# FPGA.net
KiCad netlist of a schematic drawn in Altium Designer
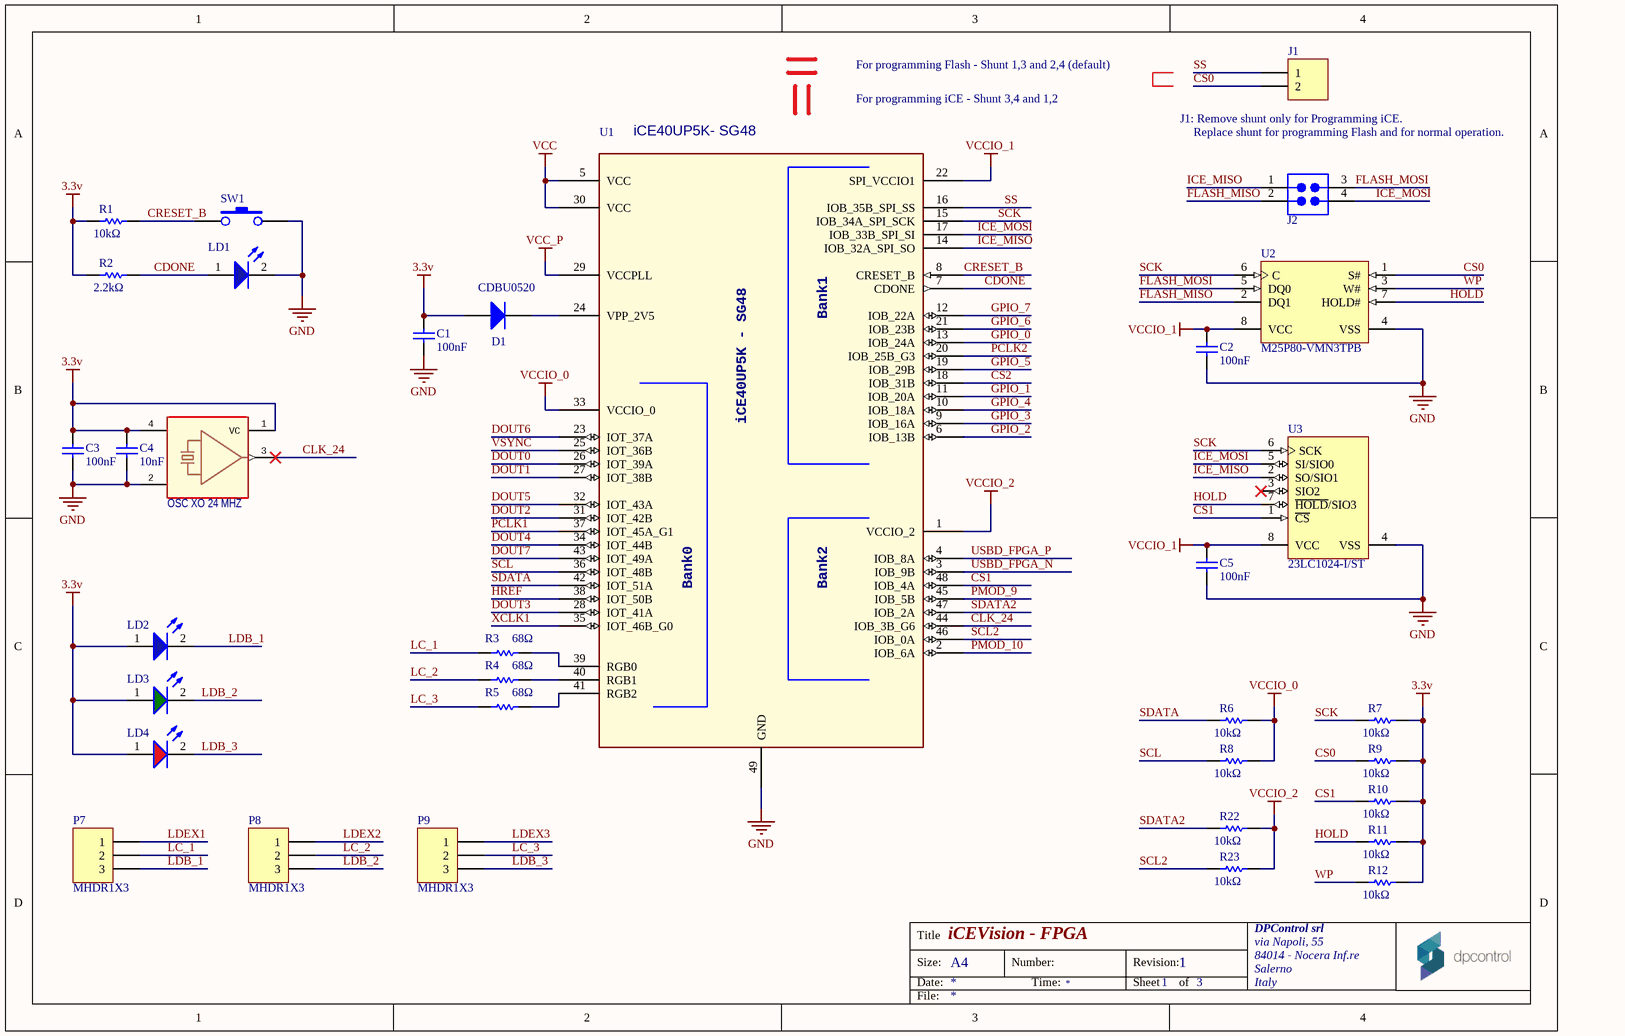
[diagram p0: FPGA.SchDoc]

(export (version "E")
  (design (tool "Eeschema 10.0.6"))
  (components
    (comp (ref "C1")
      (value "100nF")
      (footprint "0603")
      (description "Ceramic Chip Capacitor - Standard")
      (fields
        (field (name "PART NO") "C0603C104K8RACTU")
        (field (name "MPN") "GPC0603104")
        (field (name "PUBLISHER") "Altium Limited")
      )
      (libsource (lib "KEMET Chip Capacitor") (part "C0603"))
    )
    (comp (ref "C2")
      (value "100nF")
      (footprint "0603")
      (description "Ceramic Chip Capacitor - Standard")
      (fields
        (field (name "PART NO") "C0603C104K8RACTU")
        (field (name "MPN") "GPC0603104")
        (field (name "PUBLISHER") "Altium Limited")
      )
      (libsource (lib "KEMET Chip Capacitor") (part "C0603"))
    )
    (comp (ref "C3")
      (value "100nF")
      (footprint "0603")
      (description "Ceramic Chip Capacitor - Standard")
      (fields
        (field (name "PART NO") "C0603C104K8RACTU")
        (field (name "MPN") "GPC0603104")
        (field (name "PUBLISHER") "Altium Limited")
      )
      (libsource (lib "KEMET Chip Capacitor") (part "C0603"))
    )
    (comp (ref "C4")
      (value "10nF")
      (footprint "0603")
      (description "Ceramic Chip Capacitor - Standard")
      (fields
        (field (name "PART NO") "C0603C103K5RACTU")
        (field (name "MPN") "GPC0603103")
        (field (name "PUBLISHER") "Altium Limited")
      )
      (libsource (lib "KEMET Chip Capacitor") (part "C0603"))
    )
    (comp (ref "C5")
      (value "100nF")
      (footprint "0603")
      (description "Ceramic Chip Capacitor - Standard")
      (fields
        (field (name "PART NO") "C0603C104K8RACTU")
        (field (name "MPN") "GPC0603104")
        (field (name "PUBLISHER") "Altium Limited")
      )
      (libsource (lib "KEMET Chip Capacitor") (part "C0603"))
    )
    (comp (ref "D1")
      (value "CDBU0520")
      (footprint "0603")
      (description "Default Diode")
      (fields
        (field (name "MANUFACTURER") "COMCHIP TECHNOLOGY")
        (field (name "Comment") "Diode")
        (field (name "PUBLISHER") "Altium Limited")
      )
      (libsource (lib "Miscellaneous Devices_DPC") (part "Diode"))
    )
    (comp (ref "J1")
      (value "WE-2.54 mm Pin Header & Jumper 61300211121")
      (footprint "61300211121")
      (description "WR-PHD 2.54mm Pin Header")
      (fields
        (field (name "MANUFACTURER") "Würth Elektronik eiSos GmbH")
        (field (name "PARTNO") "61300211121")
        (field (name "CREATED BY") "Karrer Zheng")
      )
      (libsource (lib "WE_WR-PHD_Pin Header_2.54mm_rev15c") (part "WE-2.54 mm Pin Header & Jumper 61300211121"))
    )
    (comp (ref "J2")
      (value "WE-2.54 mm Pin Header & Jumper 61300421121")
      (footprint "61300421121")
      (description "WR-PHD 2.54 mm Dual Pin Header")
      (fields
        (field (name "MANUFACTURER") "Würth Elektronik eiSos GmbH")
        (field (name "PARTNO") "61300421121")
        (field (name "CREATED BY") "Karrer Zheng")
      )
      (libsource (lib "WE_WR-PHD_Pin Header_2.54mm_rev15c") (part "WE-2.54 mm Pin Header & Jumper 61300421121"))
    )
    (comp (ref "LD1")
      (value "150060BS75000")
      (footprint "LED_0603_Blue")
      (description "SMD mono-color Chip LED, WL-SMCW, Blue")
      (fields
        (field (name "MANUFACTURER") "W黵th Elektronik eiSos GmbH")
        (field (name "CREATED BY") "Christin Otto")
      )
      (libsource (lib "WL-LEDsmd") (part "WL-SMCW 0603  150060BS75000"))
    )
    (comp (ref "LD2")
      (value "150060BS75000")
      (footprint "LED_0603_Blue")
      (description "SMD mono-color Chip LED, WL-SMCW, Blue")
      (fields
        (field (name "MANUFACTURER") "W黵th Elektronik eiSos GmbH")
        (field (name "CREATED BY") "Christin Otto")
      )
      (libsource (lib "WL-LEDsmd") (part "WL-SMCW 0603  150060BS75000"))
    )
    (comp (ref "LD3")
      (value "150060GS75000")
      (footprint "LED_0603_Green")
      (description "SMD mono-color Chip LED, WL-SMCW, Green")
      (fields
        (field (name "MANUFACTURER") "W黵th Elektronik eiSos GmbH")
        (field (name "CREATED BY") "Christin Otto")
      )
      (libsource (lib "WL-LEDsmd") (part "WL-SMCW 0603  150060GS75000"))
    )
    (comp (ref "LD4")
      (value "150060RS75000")
      (footprint "LED_0603_Red")
      (description "SMD mono-color Chip LED, WL-SMCW, Red")
      (fields
        (field (name "MANUFACTURER") "W黵th Elektronik eiSos GmbH")
        (field (name "CREATED BY") "Christin Otto")
      )
      (libsource (lib "WL-LEDsmd") (part "WL-SMCW 0603  150060RS75000"))
    )
    (comp (ref "OSC1")
      (value "OSC XO 24 MHZ")
      (footprint "3.4X2.7-4-PAD")
      (fields
        (field (name "MANUFACTURER") "Abracon LLC")
        (field (name "PART NO") "LFSPXO025558")
        (field (name "MPN") "7M-24.000MAAJ-T")
      )
      (libsource (lib "IQD-Frequency-Products") (part "TCXO-CFPT-9301"))
    )
    (comp (ref "P7")
      (value "MHDR1X3")
      (footprint "MHDR1X3")
      (description "Header, 3-Pin")
      (fields (field (name "PUBLISHER") "Altium Limited"))
      (libsource (lib "Miscellaneous Connectors") (part "MHDR1X3"))
    )
    (comp (ref "P8")
      (value "MHDR1X3")
      (footprint "MHDR1X3")
      (description "Header, 3-Pin")
      (fields (field (name "PUBLISHER") "Altium Limited"))
      (libsource (lib "Miscellaneous Connectors") (part "MHDR1X3"))
    )
    (comp (ref "P9")
      (value "MHDR1X3")
      (footprint "MHDR1X3")
      (description "Header, 3-Pin")
      (fields (field (name "PUBLISHER") "Altium Limited"))
      (libsource (lib "Miscellaneous Connectors") (part "MHDR1X3"))
    )
    (comp (ref "R1")
      (value "10kΩ")
      (footprint "3-0603")
      (fields
        (field (name "PART NO") "ERJ3EKF1002V")
        (field (name "MPN") "GPR060310K")
        (field (name "Comment") "ERJ3EK")
        (field (name "PUBLISHER") "Altium Limited")
      )
      (libsource (lib "Panasonic Resistor") (part "ERJ3EK"))
    )
    (comp (ref "R2")
      (value "2.2kΩ")
      (footprint "3-0603")
      (fields
        (field (name "PART NO") "ERA3ARB222V")
        (field (name "MPN") "GPR06032K2")
        (field (name "Comment") "ERJ3EK")
        (field (name "PUBLISHER") "Altium Limited")
      )
      (libsource (lib "Panasonic Resistor") (part "ERJ3EK"))
    )
    (comp (ref "R3")
      (value "68Ω")
      (footprint "3-0603")
      (fields
        (field (name "PART NO") "ERJPA3F68R0V")
        (field (name "MPN") "GPR060368R")
        (field (name "Comment") "ERJ3EK")
        (field (name "PUBLISHER") "Altium Limited")
      )
      (libsource (lib "Panasonic Resistor") (part "ERJ3EK"))
    )
    (comp (ref "R4")
      (value "68Ω")
      (footprint "3-0603")
      (fields
        (field (name "PART NO") "ERJPA3F68R0V")
        (field (name "MPN") "GPR060368R")
        (field (name "Comment") "ERJ3EK")
        (field (name "PUBLISHER") "Altium Limited")
      )
      (libsource (lib "Panasonic Resistor") (part "ERJ3EK"))
    )
    (comp (ref "R5")
      (value "68Ω")
      (footprint "3-0603")
      (fields
        (field (name "PART NO") "ERJPA3F68R0V")
        (field (name "MPN") "GPR060368R")
        (field (name "Comment") "ERJ3EK")
        (field (name "PUBLISHER") "Altium Limited")
      )
      (libsource (lib "Panasonic Resistor") (part "ERJ3EK"))
    )
    (comp (ref "R6")
      (value "10kΩ")
      (footprint "3-0603")
      (fields
        (field (name "PART NO") "ERJ3EKF1002V")
        (field (name "MPN") "GPR060310K")
        (field (name "Comment") "ERJ3EK")
        (field (name "PUBLISHER") "Altium Limited")
      )
      (libsource (lib "Panasonic Resistor") (part "ERJ3EK"))
    )
    (comp (ref "R7")
      (value "10kΩ")
      (footprint "3-0603")
      (fields
        (field (name "PART NO") "ERJ3EKF1002V")
        (field (name "MPN") "GPR060310K")
        (field (name "Comment") "ERJ3EK")
        (field (name "PUBLISHER") "Altium Limited")
      )
      (libsource (lib "Panasonic Resistor") (part "ERJ3EK"))
    )
    (comp (ref "R8")
      (value "10kΩ")
      (footprint "3-0603")
      (fields
        (field (name "PART NO") "ERJ3EKF1002V")
        (field (name "MPN") "GPR060310K")
        (field (name "Comment") "ERJ3EK")
        (field (name "PUBLISHER") "Altium Limited")
      )
      (libsource (lib "Panasonic Resistor") (part "ERJ3EK"))
    )
    (comp (ref "R9")
      (value "10kΩ")
      (footprint "3-0603")
      (fields
        (field (name "PART NO") "ERJ3EKF1002V")
        (field (name "MPN") "GPR060310K")
        (field (name "Comment") "ERJ3EK")
        (field (name "PUBLISHER") "Altium Limited")
      )
      (libsource (lib "Panasonic Resistor") (part "ERJ3EK"))
    )
    (comp (ref "R10")
      (value "10kΩ")
      (footprint "3-0603")
      (fields
        (field (name "PART NO") "ERJ3EKF1002V")
        (field (name "MPN") "GPR060310K")
        (field (name "Comment") "ERJ3EK")
        (field (name "PUBLISHER") "Altium Limited")
      )
      (libsource (lib "Panasonic Resistor") (part "ERJ3EK"))
    )
    (comp (ref "R11")
      (value "10kΩ")
      (footprint "3-0603")
      (fields
        (field (name "PART NO") "ERJ3EKF1002V")
        (field (name "MPN") "GPR060310K")
        (field (name "Comment") "ERJ3EK")
        (field (name "PUBLISHER") "Altium Limited")
      )
      (libsource (lib "Panasonic Resistor") (part "ERJ3EK"))
    )
    (comp (ref "R12")
      (value "10kΩ")
      (footprint "3-0603")
      (fields
        (field (name "PART NO") "ERJ3EKF1002V")
        (field (name "MPN") "GPR060310K")
        (field (name "Comment") "ERJ3EK")
        (field (name "PUBLISHER") "Altium Limited")
      )
      (libsource (lib "Panasonic Resistor") (part "ERJ3EK"))
    )
    (comp (ref "R22")
      (value "10kΩ")
      (footprint "3-0603")
      (fields
        (field (name "PART NO") "ERJ3EKF1002V")
        (field (name "MPN") "GPR060310K")
        (field (name "Comment") "ERJ3EK")
        (field (name "PUBLISHER") "Altium Limited")
      )
      (libsource (lib "Panasonic Resistor") (part "ERJ3EK"))
    )
    (comp (ref "R23")
      (value "10kΩ")
      (footprint "3-0603")
      (fields
        (field (name "PART NO") "ERJ3EKF1002V")
        (field (name "MPN") "GPR060310K")
        (field (name "Comment") "ERJ3EK")
        (field (name "PUBLISHER") "Altium Limited")
      )
      (libsource (lib "Panasonic Resistor") (part "ERJ3EK"))
    )
    (comp (ref "SW1")
      (value "B3U-1000P")
      (footprint "B3U-1000P omron")
      (description "Tact Switch")
      (libsource (lib "B3U-1000P") (part "SW-PB"))
    )
    (comp (ref "U1")
      (value "iCE40UP5K- SG48")
      (fields (field (name "MPN") "ICE40UP5K-SG48ITR50"))
      (libsource (lib "LATTICEPLDS_Library") (part "iCE40UP5K- SG48"))
    )
    (comp (ref "U2")
      (value "M25P80-VMN3TPB")
      (footprint "MICT-MN-8_N")
      (fields
        (field (name "VOLTAGE") "2.7V-3.6V ")
        (field (name "MANUFACTURER") "Micron")
        (field (name "MPN") "MX25L8006EM2I-12G")
      )
      (libsource (lib "Micron Memory Serial NOR Flash") (part "M25P80-VMN3TPB"))
    )
    (comp (ref "U3")
      (value "23LC1024-I/ST")
      (footprint "MCHP-TSSOP-ST8_N")
      (fields (field (name "MANUFACTURER") "Microchip"))
      (libsource (lib "Microchip Serial SRAM") (part "23LC1024-I/ST"))
    )
  )
  (nets
    (net (code "1") (name "/CDONE") (class "Default")
      (node (ref "LD1") (pin "1") (pinfunction "A_1") (pintype "passive"))
      (node (ref "R2") (pin "2") (pinfunction "2_2") (pintype "passive"))
      (node (ref "U1") (pin "7") (pinfunction "CDONE_7") (pintype "output"))
    )
    (net (code "2") (name "/CLK_24") (class "Default")
      (node (ref "OSC1") (pin "3") (pinfunction "OUT_3") (pintype "output"))
      (node (ref "U1") (pin "44") (pinfunction "IOB_3B_G6_44") (pintype "bidirectional"))
    )
    (net (code "3") (name "/CRESET_B") (class "Default")
      (node (ref "R1") (pin "2") (pinfunction "2_2") (pintype "passive"))
      (node (ref "SW1") (pin "1") (pinfunction "1_1") (pintype "passive"))
      (node (ref "U1") (pin "8") (pinfunction "CRESET_B_8") (pintype "input"))
    )
    (net (code "4") (name "/CS0") (class "Default")
      (node (ref "J1") (pin "2") (pinfunction "2_2") (pintype "passive"))
      (node (ref "R9") (pin "1") (pinfunction "1_1") (pintype "passive"))
      (node (ref "U2") (pin "1") (pinfunction "S#_1") (pintype "input"))
    )
    (net (code "5") (name "/CS1") (class "Default")
      (node (ref "R10") (pin "1") (pinfunction "1_1") (pintype "passive"))
      (node (ref "U1") (pin "48") (pinfunction "IOB_4A_48") (pintype "bidirectional"))
      (node (ref "U3") (pin "1") (pinfunction "~{CS}_1") (pintype "input"))
    )
    (net (code "6") (name "/CS2") (class "Default")
      (node (ref "U1") (pin "18") (pinfunction "IOB_31B_18") (pintype "bidirectional"))
    )
    (net (code "7") (name "/DOUT0") (class "Default")
      (node (ref "U1") (pin "26") (pinfunction "IOT_39A_26") (pintype "bidirectional"))
    )
    (net (code "8") (name "/DOUT1") (class "Default")
      (node (ref "U1") (pin "27") (pinfunction "IOT_38B_27") (pintype "bidirectional"))
    )
    (net (code "9") (name "/DOUT2") (class "Default")
      (node (ref "U1") (pin "31") (pinfunction "IOT_42B_31") (pintype "bidirectional"))
    )
    (net (code "10") (name "/DOUT3") (class "Default")
      (node (ref "U1") (pin "28") (pinfunction "IOT_41A_28") (pintype "bidirectional"))
    )
    (net (code "11") (name "/DOUT4") (class "Default")
      (node (ref "U1") (pin "34") (pinfunction "IOT_44B_34") (pintype "bidirectional"))
    )
    (net (code "12") (name "/DOUT5") (class "Default")
      (node (ref "U1") (pin "32") (pinfunction "IOT_43A_32") (pintype "bidirectional"))
    )
    (net (code "13") (name "/DOUT6") (class "Default")
      (node (ref "U1") (pin "23") (pinfunction "IOT_37A_23") (pintype "bidirectional"))
    )
    (net (code "14") (name "/DOUT7") (class "Default")
      (node (ref "U1") (pin "43") (pinfunction "IOT_49A_43") (pintype "bidirectional"))
    )
    (net (code "15") (name "/FLASH_MISO") (class "Default")
      (node (ref "J2") (pin "2") (pinfunction "1_2") (pintype "passive"))
      (node (ref "U2") (pin "2") (pinfunction "DQ1_2") (pintype "tri_state"))
    )
    (net (code "16") (name "/FLASH_MOSI") (class "Default")
      (node (ref "J2") (pin "3") (pinfunction "3_3") (pintype "passive"))
      (node (ref "U2") (pin "5") (pinfunction "DQ0_5") (pintype "input"))
    )
    (net (code "17") (name "/GPIO_0") (class "Default")
      (node (ref "U1") (pin "13") (pinfunction "IOB_24A_13") (pintype "bidirectional"))
    )
    (net (code "18") (name "/GPIO_1") (class "Default")
      (node (ref "U1") (pin "11") (pinfunction "IOB_20A_11") (pintype "bidirectional"))
    )
    (net (code "19") (name "/GPIO_2") (class "Default")
      (node (ref "U1") (pin "6") (pinfunction "IOB_13B_6") (pintype "bidirectional"))
    )
    (net (code "20") (name "/GPIO_3") (class "Default")
      (node (ref "U1") (pin "9") (pinfunction "IOB_16A_9") (pintype "bidirectional"))
    )
    (net (code "21") (name "/GPIO_4") (class "Default")
      (node (ref "U1") (pin "10") (pinfunction "IOB_18A_10") (pintype "bidirectional"))
    )
    (net (code "22") (name "/GPIO_5") (class "Default")
      (node (ref "U1") (pin "19") (pinfunction "IOB_29B_19") (pintype "bidirectional"))
    )
    (net (code "23") (name "/GPIO_6") (class "Default")
      (node (ref "U1") (pin "21") (pinfunction "IOB_23B_21") (pintype "bidirectional"))
    )
    (net (code "24") (name "/GPIO_7") (class "Default")
      (node (ref "U1") (pin "12") (pinfunction "IOB_22A_12") (pintype "bidirectional"))
    )
    (net (code "25") (name "/HOLD") (class "Default")
      (node (ref "R11") (pin "1") (pinfunction "1_1") (pintype "passive"))
      (node (ref "U2") (pin "7") (pinfunction "HOLD#_7") (pintype "input"))
      (node (ref "U3") (pin "7") (pinfunction "~{HOLD}/SIO3_7") (pintype "bidirectional"))
    )
    (net (code "26") (name "/HREF") (class "Default")
      (node (ref "U1") (pin "38") (pinfunction "IOT_50B_38") (pintype "bidirectional"))
    )
    (net (code "27") (name "/ICE_MISO") (class "Default")
      (node (ref "J2") (pin "1") (pinfunction "2_1") (pintype "passive"))
      (node (ref "U1") (pin "14") (pinfunction "IOB_32A_SPI_SO_14") (pintype "passive"))
      (node (ref "U3") (pin "2") (pinfunction "SO/SIO1_2") (pintype "bidirectional"))
    )
    (net (code "28") (name "/ICE_MOSI") (class "Default")
      (node (ref "J2") (pin "4") (pinfunction "4_4") (pintype "passive"))
      (node (ref "U1") (pin "17") (pinfunction "IOB_33B_SPI_SI_17") (pintype "passive"))
      (node (ref "U3") (pin "5") (pinfunction "SI/SIO0_5") (pintype "bidirectional"))
    )
    (net (code "29") (name "/LC_1") (class "Default")
      (node (ref "P7") (pin "2") (pinfunction "2_2") (pintype "passive"))
      (node (ref "R3") (pin "1") (pinfunction "1_1") (pintype "passive"))
    )
    (net (code "30") (name "/LC_2") (class "Default")
      (node (ref "P8") (pin "2") (pinfunction "2_2") (pintype "passive"))
      (node (ref "R4") (pin "1") (pinfunction "1_1") (pintype "passive"))
    )
    (net (code "31") (name "/LC_3") (class "Default")
      (node (ref "P9") (pin "2") (pinfunction "2_2") (pintype "passive"))
      (node (ref "R5") (pin "1") (pinfunction "1_1") (pintype "passive"))
    )
    (net (code "32") (name "/LDB_1") (class "Default")
      (node (ref "LD2") (pin "2") (pinfunction "C_2") (pintype "passive"))
      (node (ref "P7") (pin "3") (pinfunction "3_3") (pintype "passive"))
    )
    (net (code "33") (name "/LDB_2") (class "Default")
      (node (ref "LD3") (pin "2") (pinfunction "C_2") (pintype "passive"))
      (node (ref "P8") (pin "3") (pinfunction "3_3") (pintype "passive"))
    )
    (net (code "34") (name "/LDB_3") (class "Default")
      (node (ref "LD4") (pin "2") (pinfunction "C_2") (pintype "passive"))
      (node (ref "P9") (pin "3") (pinfunction "3_3") (pintype "passive"))
    )
    (net (code "35") (name "/LDEX1") (class "Default")
      (node (ref "P7") (pin "1") (pinfunction "1_1") (pintype "passive"))
    )
    (net (code "36") (name "/LDEX2") (class "Default")
      (node (ref "P8") (pin "1") (pinfunction "1_1") (pintype "passive"))
    )
    (net (code "37") (name "/LDEX3") (class "Default")
      (node (ref "P9") (pin "1") (pinfunction "1_1") (pintype "passive"))
    )
    (net (code "38") (name "/PCLK1") (class "Default")
      (node (ref "U1") (pin "37") (pinfunction "IOT_45A_G1_37") (pintype "bidirectional"))
    )
    (net (code "39") (name "/PCLK2") (class "Default")
      (node (ref "U1") (pin "20") (pinfunction "IOB_25B_G3_20") (pintype "bidirectional"))
    )
    (net (code "40") (name "/PMOD_9") (class "Default")
      (node (ref "U1") (pin "45") (pinfunction "IOB_5B_45") (pintype "bidirectional"))
    )
    (net (code "41") (name "/PMOD_10") (class "Default")
      (node (ref "U1") (pin "2") (pinfunction "IOB_6A_2") (pintype "bidirectional"))
    )
    (net (code "42") (name "/SCK") (class "Default")
      (node (ref "R7") (pin "1") (pinfunction "1_1") (pintype "passive"))
      (node (ref "U1") (pin "15") (pinfunction "IOB_34A_SPI_SCK_15") (pintype "passive"))
      (node (ref "U2") (pin "6") (pinfunction "C_6") (pintype "input"))
      (node (ref "U3") (pin "6") (pinfunction "SCK_6") (pintype "input"))
    )
    (net (code "43") (name "/SCL") (class "Default")
      (node (ref "R8") (pin "1") (pinfunction "1_1") (pintype "passive"))
      (node (ref "U1") (pin "36") (pinfunction "IOT_48B_36") (pintype "bidirectional"))
    )
    (net (code "44") (name "/SCL2") (class "Default")
      (node (ref "R23") (pin "1") (pinfunction "1_1") (pintype "passive"))
      (node (ref "U1") (pin "46") (pinfunction "IOB_0A_46") (pintype "bidirectional"))
    )
    (net (code "45") (name "/SDATA") (class "Default")
      (node (ref "R6") (pin "1") (pinfunction "1_1") (pintype "passive"))
      (node (ref "U1") (pin "42") (pinfunction "IOT_51A_42") (pintype "bidirectional"))
    )
    (net (code "46") (name "/SDATA2") (class "Default")
      (node (ref "R22") (pin "1") (pinfunction "1_1") (pintype "passive"))
      (node (ref "U1") (pin "47") (pinfunction "IOB_2A_47") (pintype "bidirectional"))
    )
    (net (code "47") (name "/SS") (class "Default")
      (node (ref "J1") (pin "1") (pinfunction "1_1") (pintype "passive"))
      (node (ref "U1") (pin "16") (pinfunction "IOB_35B_SPI_SS_16") (pintype "passive"))
    )
    (net (code "48") (name "/USBD_FPGA_N") (class "Default")
      (node (ref "U1") (pin "3") (pinfunction "IOB_9B_3") (pintype "bidirectional"))
    )
    (net (code "49") (name "/USBD_FPGA_P") (class "Default")
      (node (ref "U1") (pin "4") (pinfunction "IOB_8A_4") (pintype "bidirectional"))
    )
    (net (code "50") (name "/VSYNC") (class "Default")
      (node (ref "U1") (pin "25") (pinfunction "IOT_36B_25") (pintype "bidirectional"))
    )
    (net (code "51") (name "/WP") (class "Default")
      (node (ref "R12") (pin "1") (pinfunction "1_1") (pintype "passive"))
      (node (ref "U2") (pin "3") (pinfunction "W#_3") (pintype "input"))
    )
    (net (code "52") (name "/XCLK1") (class "Default")
      (node (ref "U1") (pin "35") (pinfunction "IOT_46B_G0_35") (pintype "bidirectional"))
    )
    (net (code "53") (name "3.3v") (class "Default")
      (node (ref "C1") (pin "2") (pinfunction "2_2") (pintype "passive"))
      (node (ref "C3") (pin "1") (pinfunction "1_1") (pintype "passive"))
      (node (ref "C4") (pin "2") (pinfunction "2_2") (pintype "passive"))
      (node (ref "D1") (pin "1") (pinfunction "A_1") (pintype "passive"))
      (node (ref "LD2") (pin "1") (pinfunction "A_1") (pintype "passive"))
      (node (ref "LD3") (pin "1") (pinfunction "A_1") (pintype "passive"))
      (node (ref "LD4") (pin "1") (pinfunction "A_1") (pintype "passive"))
      (node (ref "OSC1") (pin "1") (pinfunction "VC_1") (pintype "passive"))
      (node (ref "OSC1") (pin "4") (pinfunction "VCC_4") (pintype "power_in"))
      (node (ref "R1") (pin "1") (pinfunction "1_1") (pintype "passive"))
      (node (ref "R10") (pin "2") (pinfunction "2_2") (pintype "passive"))
      (node (ref "R11") (pin "2") (pinfunction "2_2") (pintype "passive"))
      (node (ref "R12") (pin "2") (pinfunction "2_2") (pintype "passive"))
      (node (ref "R2") (pin "1") (pinfunction "1_1") (pintype "passive"))
      (node (ref "R7") (pin "2") (pinfunction "2_2") (pintype "passive"))
      (node (ref "R9") (pin "2") (pinfunction "2_2") (pintype "passive"))
    )
    (net (code "54") (name "GND") (class "Default")
      (node (ref "C1") (pin "1") (pinfunction "1_1") (pintype "passive"))
      (node (ref "C2") (pin "1") (pinfunction "1_1") (pintype "passive"))
      (node (ref "C3") (pin "2") (pinfunction "2_2") (pintype "passive"))
      (node (ref "C4") (pin "1") (pinfunction "1_1") (pintype "passive"))
      (node (ref "C5") (pin "1") (pinfunction "1_1") (pintype "passive"))
      (node (ref "LD1") (pin "2") (pinfunction "C_2") (pintype "passive"))
      (node (ref "OSC1") (pin "2") (pinfunction "GND_2") (pintype "power_in"))
      (node (ref "SW1") (pin "2") (pinfunction "2_2") (pintype "passive"))
      (node (ref "U1") (pin "49") (pinfunction "GND_49") (pintype "power_in"))
      (node (ref "U2") (pin "4") (pinfunction "VSS_4") (pintype "power_in"))
      (node (ref "U3") (pin "4") (pinfunction "VSS_4") (pintype "power_in"))
    )
    (net (code "55") (name "Net-(D1-K)") (class "Default")
      (node (ref "D1") (pin "2") (pinfunction "K_2") (pintype "passive"))
      (node (ref "U1") (pin "24") (pinfunction "VPP_2V5_24") (pintype "power_in"))
    )
    (net (code "56") (name "Net-(U1-RGB0)") (class "Default")
      (node (ref "R3") (pin "2") (pinfunction "2_2") (pintype "passive"))
      (node (ref "U1") (pin "39") (pinfunction "RGB0_39") (pintype "open_collector"))
    )
    (net (code "57") (name "Net-(U1-RGB1)") (class "Default")
      (node (ref "R4") (pin "2") (pinfunction "2_2") (pintype "passive"))
      (node (ref "U1") (pin "40") (pinfunction "RGB1_40") (pintype "open_collector"))
    )
    (net (code "58") (name "Net-(U1-RGB2)") (class "Default")
      (node (ref "R5") (pin "2") (pinfunction "2_2") (pintype "passive"))
      (node (ref "U1") (pin "41") (pinfunction "RGB2_41") (pintype "open_collector"))
    )
    (net (code "59") (name "VCC") (class "Default")
      (node (ref "U1") (pin "30") (pinfunction "VCC_30") (pintype "power_in"))
      (node (ref "U1") (pin "5") (pinfunction "VCC_5") (pintype "power_in"))
    )
    (net (code "60") (name "VCCIO_0") (class "Default")
      (node (ref "R6") (pin "2") (pinfunction "2_2") (pintype "passive"))
      (node (ref "R8") (pin "2") (pinfunction "2_2") (pintype "passive"))
      (node (ref "U1") (pin "33") (pinfunction "VCCIO_0_33") (pintype "power_in"))
    )
    (net (code "61") (name "VCCIO_1") (class "Default")
      (node (ref "C2") (pin "2") (pinfunction "2_2") (pintype "passive"))
      (node (ref "C5") (pin "2") (pinfunction "2_2") (pintype "passive"))
      (node (ref "U1") (pin "22") (pinfunction "SPI_VCCIO1_22") (pintype "power_in"))
      (node (ref "U2") (pin "8") (pinfunction "VCC_8") (pintype "power_in"))
      (node (ref "U3") (pin "8") (pinfunction "VCC_8") (pintype "power_in"))
    )
    (net (code "62") (name "VCCIO_2") (class "Default")
      (node (ref "R22") (pin "2") (pinfunction "2_2") (pintype "passive"))
      (node (ref "R23") (pin "2") (pinfunction "2_2") (pintype "passive"))
      (node (ref "U1") (pin "1") (pinfunction "VCCIO_2_1") (pintype "power_in"))
    )
    (net (code "63") (name "VCC_P") (class "Default")
      (node (ref "U1") (pin "29") (pinfunction "VCCPLL_29") (pintype "power_in"))
    )
    (net (code "64") (name "unconnected-(U3-SIO2-Pad3)") (class "Default")
      (node (ref "U3") (pin "3") (pinfunction "SIO2_3") (pintype "bidirectional+no_connect"))
    )
  )
)
